# pcc_circuit_example.net
KiCad netlist of a schematic drawn in EAGLE
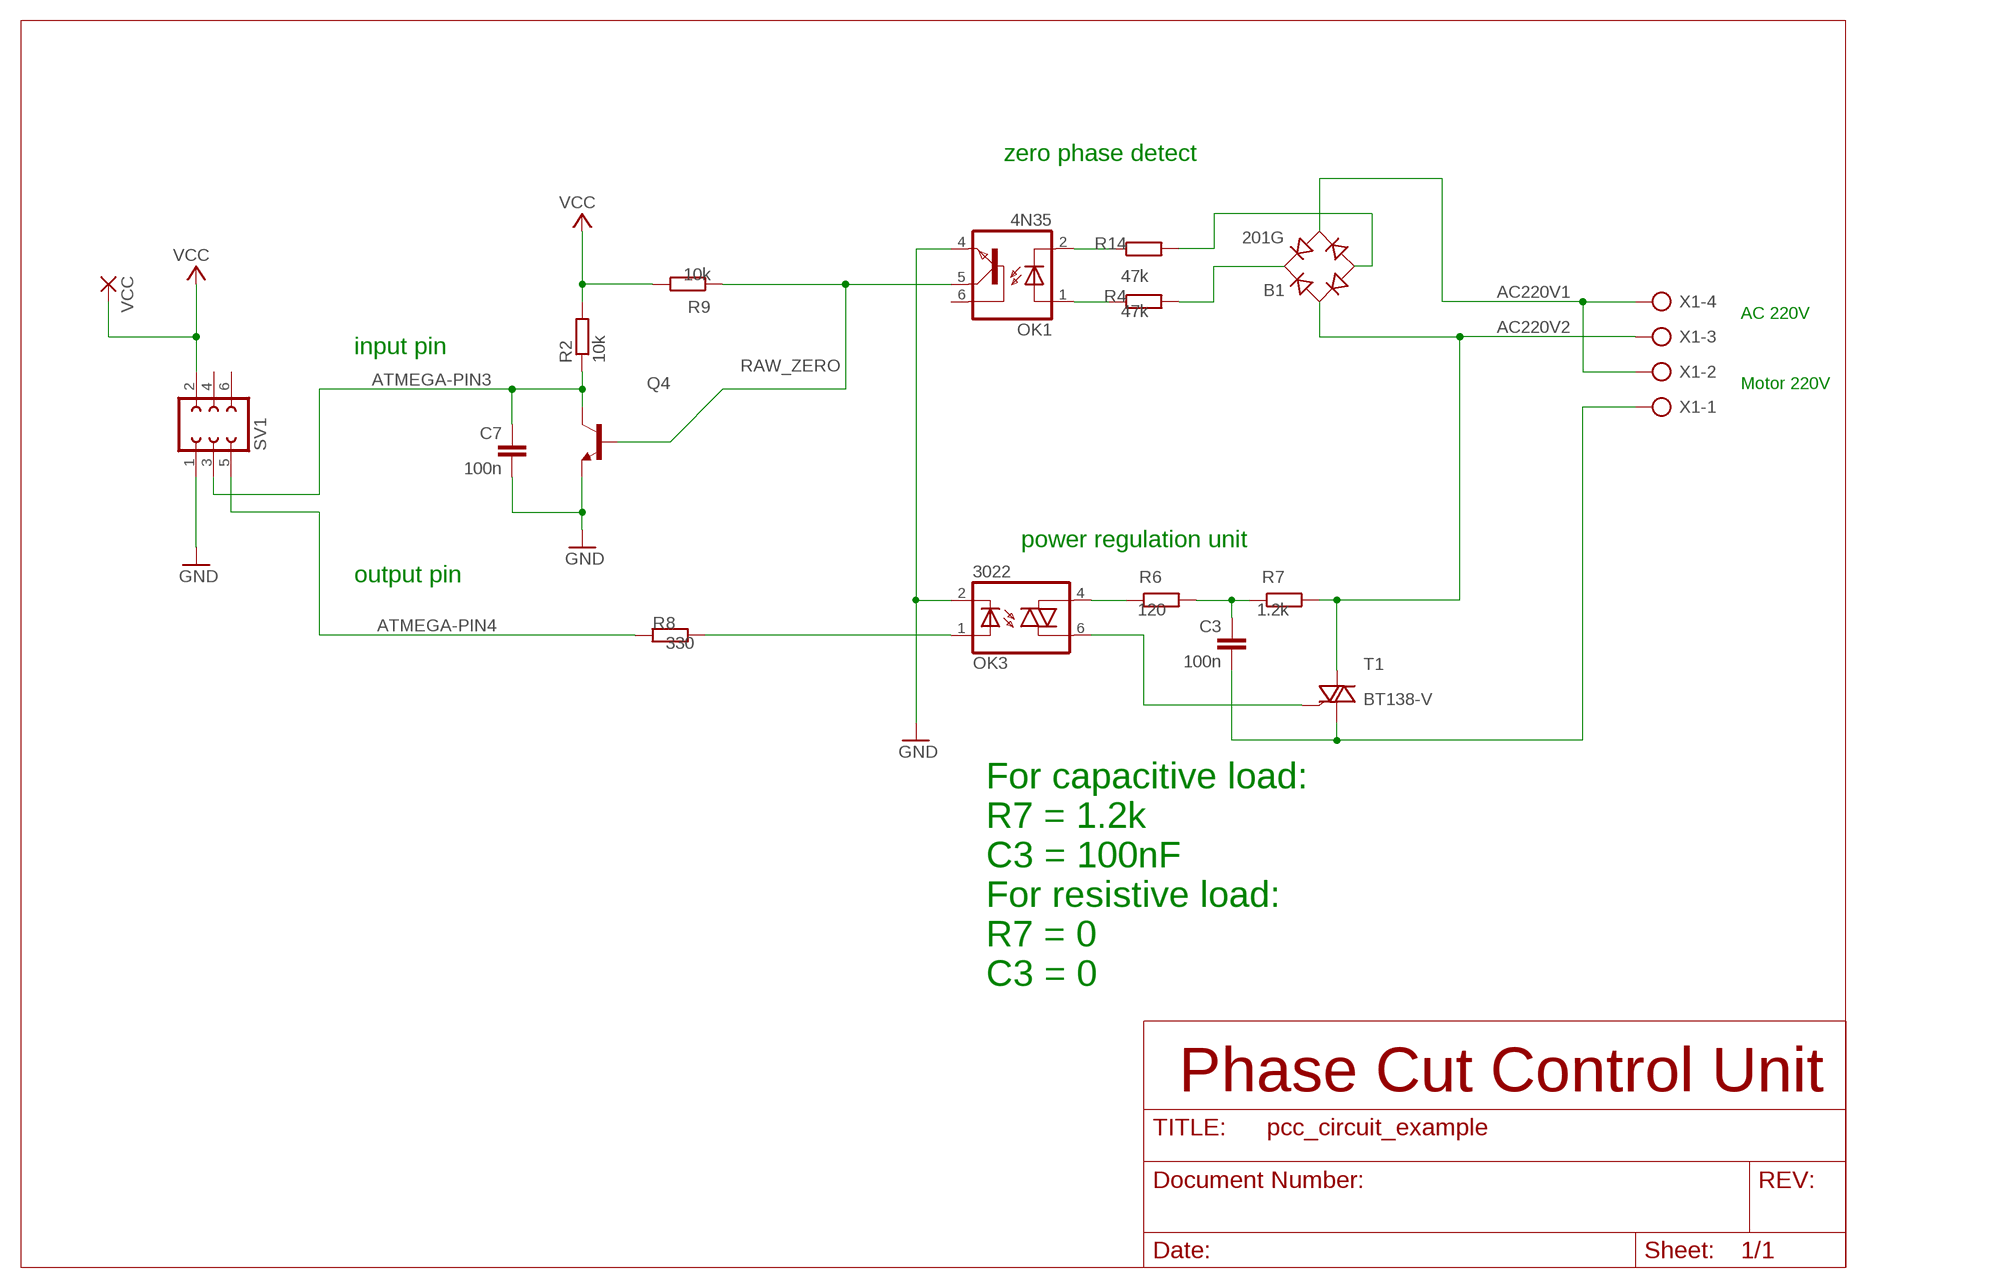
[diagram p0: schematic, sheet 1]

(export (version "E")
  (design (tool "Eeschema 10.0.6"))
  (components
    (comp (ref "B1")
      (value "201G")
      (footprint "eagle-import:RB1A")
      (libsource (lib "eagle-import") (part "RB1A"))
    )
    (comp (ref "C3")
      (value "100n")
      (footprint "eagle-import:C15B5")
      (libsource (lib "eagle-import") (part "C15/5"))
    )
    (comp (ref "C7")
      (value "100n")
      (footprint "eagle-import:C050-024X044")
      (libsource (lib "eagle-import") (part "C-55MM"))
    )
    (comp (ref "OK1")
      (value "4N35")
      (footprint "eagle-import:DIL06")
      (fields (field (name "MF") "FAIRCHILD SEMICONDUCTOR"))
      (libsource (lib "eagle-import") (part "4N35"))
    )
    (comp (ref "OK3")
      (value "3022")
      (footprint "eagle-import:DIL06")
      (fields (field (name "MF") "VISHAY/TELEFUNKEN") (field (name "MPN") "IL420"))
      (libsource (lib "eagle-import") (part "IL420"))
    )
    (comp (ref "Q4")
      (value "BC548")
      (footprint "eagle-import:TO92-EBC")
      (libsource (lib "eagle-import") (part "BC548"))
    )
    (comp (ref "R2")
      (value "10k")
      (footprint "eagle-import:R_0207_2V")
      (libsource (lib "eagle-import") (part "R-EU_0207/2V"))
    )
    (comp (ref "R4")
      (value "47k")
      (footprint "eagle-import:R_0207_2V")
      (libsource (lib "eagle-import") (part "R-EU_0207/2V"))
    )
    (comp (ref "R6")
      (value "120")
      (footprint "eagle-import:R_0207_2V")
      (libsource (lib "eagle-import") (part "R-EU_0207/2V"))
    )
    (comp (ref "R7")
      (value "1.2k")
      (footprint "eagle-import:R_0207_2V")
      (libsource (lib "eagle-import") (part "R-EU_0207/2V"))
    )
    (comp (ref "R8")
      (value "330")
      (footprint "eagle-import:R_0207_2V")
      (libsource (lib "eagle-import") (part "R-EU_0207/2V"))
    )
    (comp (ref "R9")
      (value "10k")
      (footprint "eagle-import:R_0207_2V")
      (libsource (lib "eagle-import") (part "R-EU_0207/2V"))
    )
    (comp (ref "R14")
      (value "47k")
      (footprint "eagle-import:R_0207_2V")
      (libsource (lib "eagle-import") (part "R-EU_0207/2V"))
    )
    (comp (ref "SV1")
      (value "FE03-2")
      (footprint "eagle-import:FE03-2")
      (libsource (lib "eagle-import") (part "FE03-2"))
    )
    (comp (ref "T1")
      (value "BT138-V")
      (footprint "eagle-import:TO220V")
      (libsource (lib "eagle-import") (part "BT138-V"))
    )
    (comp (ref "VCC")
      (value "PAD1,6/0,8")
      (footprint "eagle-import:PAD1,6_0,8")
      (libsource (lib "eagle-import") (part "PAD1,6/0,8"))
    )
    (comp (ref "X1")
      (value "AK300/4")
      (footprint "eagle-import:AK300_4")
      (libsource (lib "eagle-import") (part "AK300/4"))
    )
  )
  (nets
    (net (code "1") (name "/AC220V1") (class "Default")
      (node (ref "B1") (pin "AC2") (pinfunction "AC2_AC2") (pintype "passive"))
      (node (ref "X1") (pin "2") (pinfunction "KL_2") (pintype "passive"))
      (node (ref "X1") (pin "4") (pinfunction "KL_4") (pintype "passive"))
    )
    (net (code "2") (name "/AC220V2") (class "Default")
      (node (ref "B1") (pin "AC1") (pinfunction "AC1_AC1") (pintype "passive"))
      (node (ref "R7") (pin "2") (pinfunction "2_2") (pintype "passive"))
      (node (ref "T1") (pin "2") (pinfunction "A2_2") (pintype "passive"))
      (node (ref "X1") (pin "3") (pinfunction "KL_3") (pintype "passive"))
    )
    (net (code "3") (name "/ATMEGA-PIN3") (class "Default")
      (node (ref "C7") (pin "1") (pinfunction "1_1") (pintype "passive"))
      (node (ref "Q4") (pin "C") (pinfunction "C_C") (pintype "passive"))
      (node (ref "R2") (pin "1") (pinfunction "1_1") (pintype "passive"))
      (node (ref "SV1") (pin "3") (pinfunction "3_3") (pintype "passive"))
    )
    (net (code "4") (name "/ATMEGA-PIN4") (class "Default")
      (node (ref "R8") (pin "2") (pinfunction "2_2") (pintype "passive"))
      (node (ref "SV1") (pin "5") (pinfunction "5_5") (pintype "passive"))
    )
    (net (code "5") (name "/RAW_ZERO") (class "Default")
      (node (ref "OK1") (pin "5") (pinfunction "COL_5") (pintype "passive"))
      (node (ref "Q4") (pin "B") (pinfunction "B_B") (pintype "passive"))
      (node (ref "R9") (pin "1") (pinfunction "1_1") (pintype "passive"))
    )
    (net (code "6") (name "GND") (class "Default")
      (node (ref "C7") (pin "2") (pinfunction "2_2") (pintype "passive"))
      (node (ref "OK1") (pin "4") (pinfunction "EMI_4") (pintype "passive"))
      (node (ref "OK3") (pin "2") (pinfunction "C_2") (pintype "passive"))
      (node (ref "Q4") (pin "E") (pinfunction "E_E") (pintype "passive"))
      (node (ref "SV1") (pin "1") (pinfunction "1_1") (pintype "passive"))
    )
    (net (code "7") (name "Net-(B1-Pad+)") (class "Default")
      (node (ref "B1") (pin "+") (pinfunction "+_+") (pintype "passive"))
      (node (ref "R4") (pin "2") (pinfunction "2_2") (pintype "passive"))
    )
    (net (code "8") (name "Net-(B1-Pad-)") (class "Default")
      (node (ref "B1") (pin "-") (pinfunction "-_-") (pintype "passive"))
      (node (ref "R14") (pin "2") (pinfunction "2_2") (pintype "passive"))
    )
    (net (code "9") (name "Net-(C3-Pad1)") (class "Default")
      (node (ref "C3") (pin "1") (pinfunction "1_1") (pintype "passive"))
      (node (ref "R6") (pin "2") (pinfunction "2_2") (pintype "passive"))
      (node (ref "R7") (pin "1") (pinfunction "1_1") (pintype "passive"))
    )
    (net (code "10") (name "Net-(OK1-A)") (class "Default")
      (node (ref "OK1") (pin "1") (pinfunction "A_1") (pintype "passive"))
      (node (ref "R4") (pin "1") (pinfunction "1_1") (pintype "passive"))
    )
    (net (code "11") (name "Net-(OK1-C)") (class "Default")
      (node (ref "OK1") (pin "2") (pinfunction "C_2") (pintype "passive"))
      (node (ref "R14") (pin "1") (pinfunction "1_1") (pintype "passive"))
    )
    (net (code "12") (name "Net-(OK3-A)") (class "Default")
      (node (ref "OK3") (pin "1") (pinfunction "A_1") (pintype "passive"))
      (node (ref "R8") (pin "1") (pinfunction "1_1") (pintype "passive"))
    )
    (net (code "13") (name "Net-(OK3-A1)") (class "Default")
      (node (ref "OK3") (pin "4") (pinfunction "A1_4") (pintype "passive"))
      (node (ref "R6") (pin "1") (pinfunction "1_1") (pintype "passive"))
    )
    (net (code "14") (name "Net-(OK3-A2)") (class "Default")
      (node (ref "OK3") (pin "6") (pinfunction "A2_6") (pintype "passive"))
      (node (ref "T1") (pin "3") (pinfunction "G_3") (pintype "passive"))
    )
    (net (code "15") (name "Net-(T1-A1)") (class "Default")
      (node (ref "C3") (pin "2") (pinfunction "2_2") (pintype "passive"))
      (node (ref "T1") (pin "1") (pinfunction "A1_1") (pintype "passive"))
      (node (ref "X1") (pin "1") (pinfunction "KL_1") (pintype "passive"))
    )
    (net (code "16") (name "VCC") (class "Default")
      (node (ref "R2") (pin "2") (pinfunction "2_2") (pintype "passive"))
      (node (ref "R9") (pin "2") (pinfunction "2_2") (pintype "passive"))
      (node (ref "SV1") (pin "2") (pinfunction "2_2") (pintype "passive"))
      (node (ref "VCC") (pin "1") (pinfunction "P_1") (pintype "passive"))
    )
    (net (code "17") (name "unconnected-(OK1-BAS-Pad6)") (class "Default")
      (node (ref "OK1") (pin "6") (pinfunction "BAS_6") (pintype "passive"))
    )
    (net (code "18") (name "unconnected-(SV1-Pad4)") (class "Default")
      (node (ref "SV1") (pin "4") (pinfunction "4_4") (pintype "passive"))
    )
    (net (code "19") (name "unconnected-(SV1-Pad6)") (class "Default")
      (node (ref "SV1") (pin "6") (pinfunction "6_6") (pintype "passive"))
    )
  )
)
